# Battery_Operated_Node.net
KiCad netlist of a schematic drawn in Altium Designer
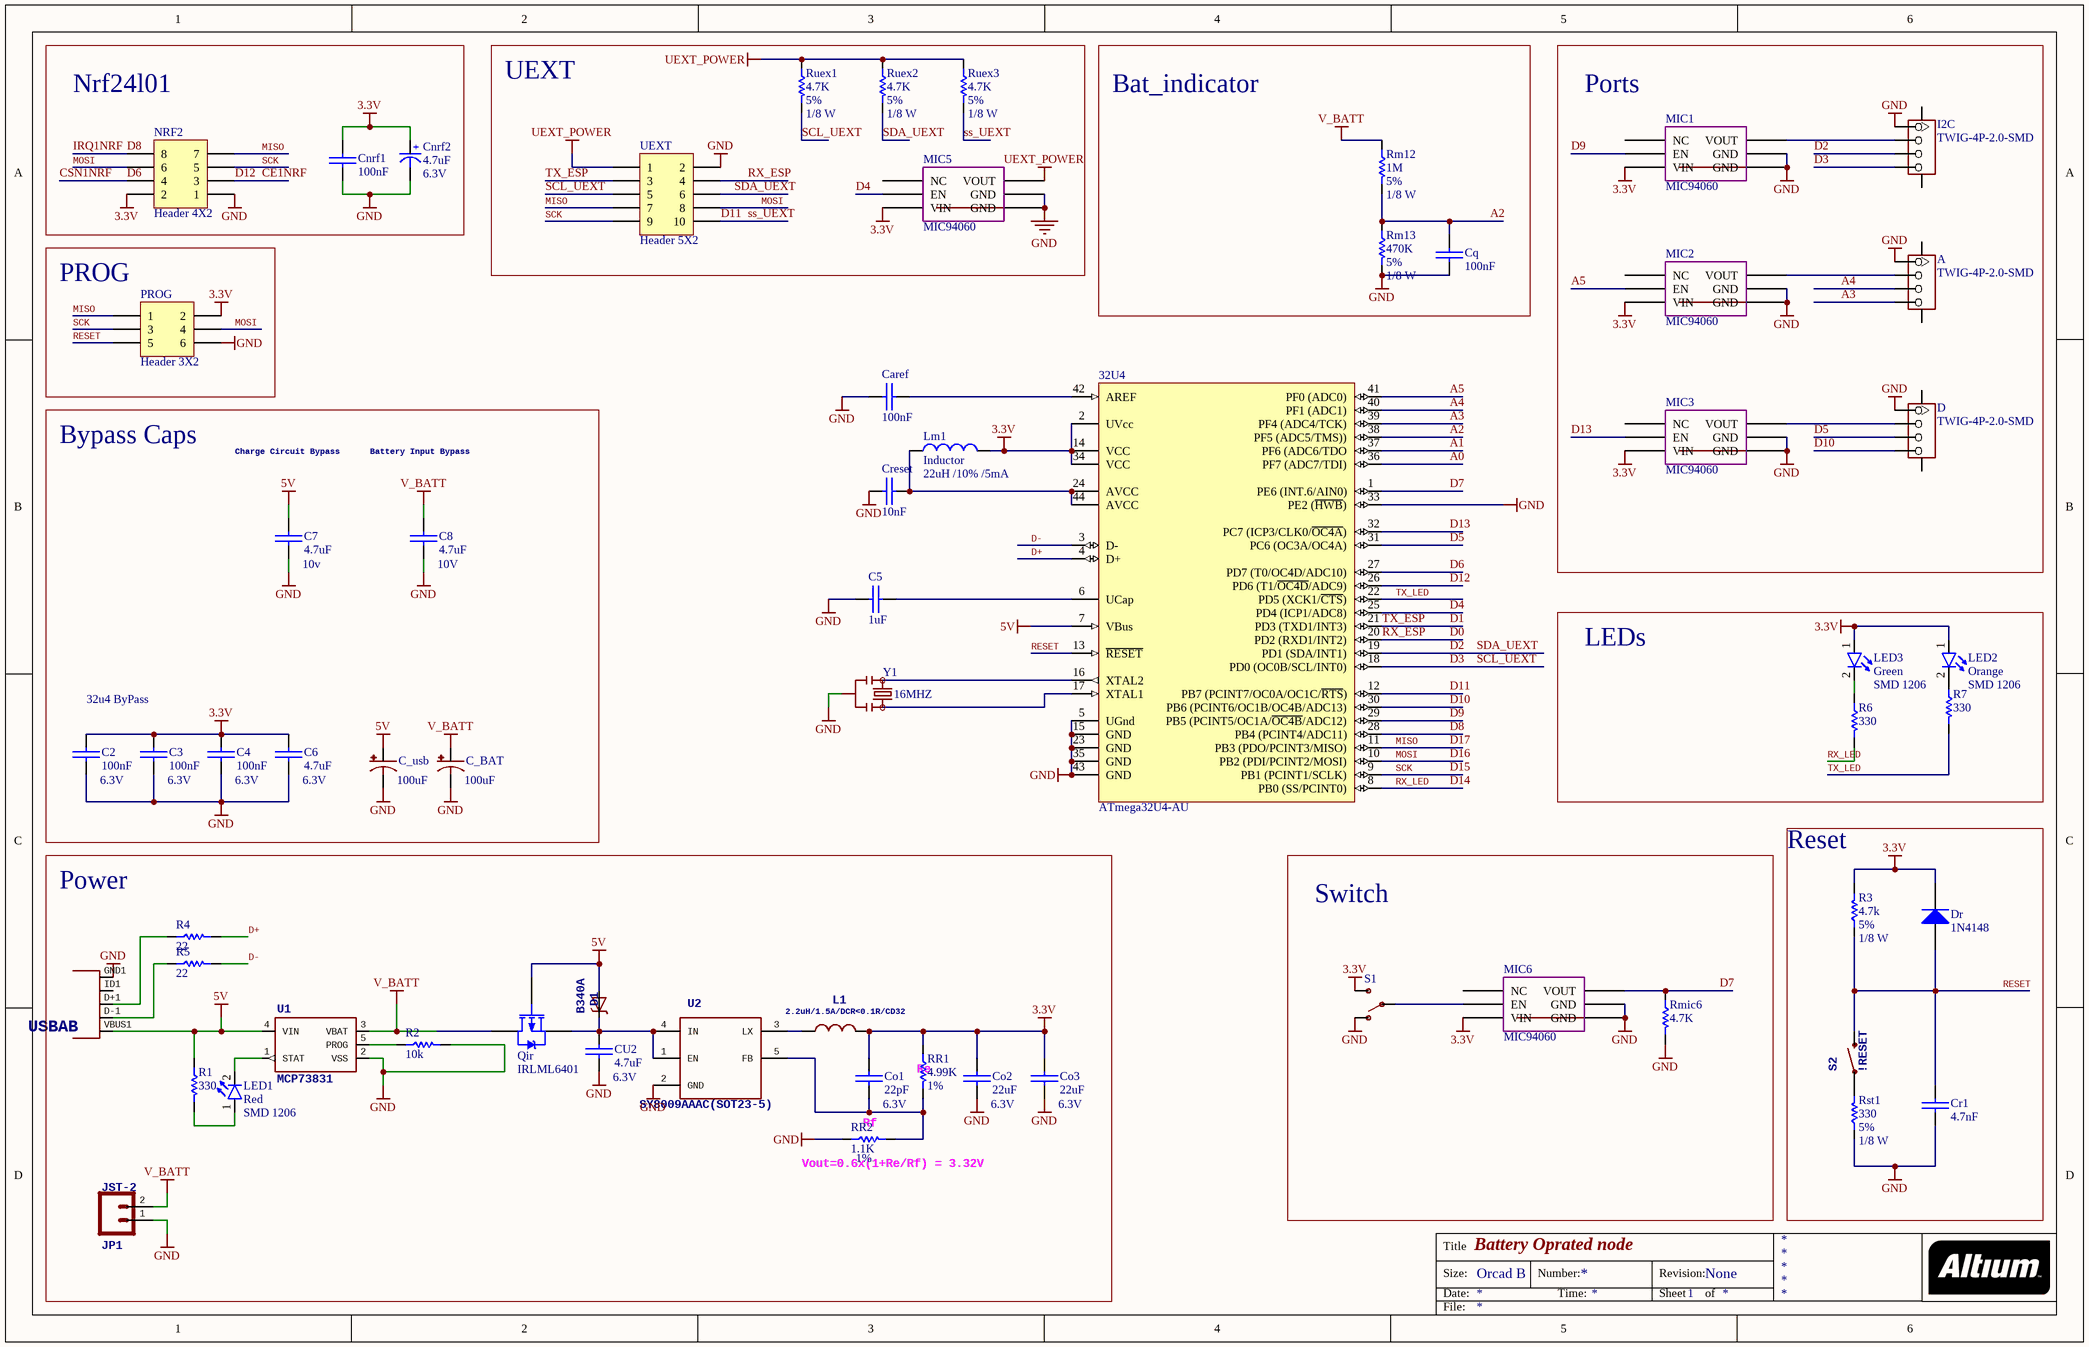
[diagram p0: Battery_Operated Node.SchDoc]

(export (version "E")
  (design (tool "Eeschema 10.0.6"))
  (components
    (comp (ref "32U4")
      (value "ATmega32U4-AU")
      (footprint "44ML_N")
      (description "8-bit AVR Microcontroller, 44-pin TQFP, Industrial Grade (-40°C to 85°C)")
      (fields (field (name "PUBLISHER") "Altium Limited"))
      (libsource (lib "Atmel Microcontroller 8-Bit megaAVR") (part "ATmega32U4-AU"))
    )
    (comp (ref "A")
      (value "TWIG-4P-2.0-SMD")
      (footprint "4P-SMD-2.0")
      (description "part num:1125S-SMT-4P URL: http://oom.lt/J204S")
      (libsource (lib "Connector") (part "TWIG-4P-2.0-SMD-FEMALE-REINFORCE'DD'"))
    )
    (comp (ref "C2")
      (value "100nF")
      (footprint "SMD_CAP_0805")
      (description "ceramic capacitor")
      (fields (field (name "VOLTAGE") "6.3V"))
      (libsource (lib "My Library") (part "Cap-Bipolar"))
    )
    (comp (ref "C3")
      (value "100nF")
      (footprint "SMD_CAP_0805")
      (description "ceramic capacitor")
      (fields (field (name "VOLTAGE") "6.3V"))
      (libsource (lib "My Library") (part "Cap-Bipolar"))
    )
    (comp (ref "C4")
      (value "100nF")
      (footprint "SMD_CAP_0805")
      (description "ceramic capacitor")
      (fields (field (name "VOLTAGE") "6.3V"))
      (libsource (lib "My Library") (part "Cap-Bipolar"))
    )
    (comp (ref "C5")
      (value "1uF")
      (footprint "SMD_CAP_0805")
      (description "ceramic capacitor")
      (fields (field (name "VOLTAGE") "6.3V"))
      (libsource (lib "My Library") (part "Cap-Bipolar"))
    )
    (comp (ref "C6")
      (value "4.7uF")
      (footprint "SMD_CAP_0805")
      (description "ceramic capacitor")
      (fields (field (name "VOLTAGE") "6.3V"))
      (libsource (lib "My Library") (part "Cap-Bipolar"))
    )
    (comp (ref "C7")
      (value "4.7uF")
      (footprint "SMD_CAP_0805")
      (description "ceramic capacitor")
      (fields (field (name "VOLTAGE") "10v"))
      (libsource (lib "My Library") (part "Cap-Bipolar"))
    )
    (comp (ref "C8")
      (value "4.7uF")
      (footprint "SMD_CAP_0805")
      (description "ceramic capacitor")
      (fields (field (name "VOLTAGE") "10V"))
      (libsource (lib "My Library") (part "Cap-Bipolar"))
    )
    (comp (ref "Caref")
      (value "100nF")
      (footprint "SMD_CAP_0805")
      (description "ceramic capacitor")
      (fields (field (name "VOLTAGE") "100V") (field (name "DESIGNER") "Saeid Jorablo"))
      (libsource (lib "My Library") (part "Cap-Bipolar"))
    )
    (comp (ref "Cnrf1")
      (value "100nF")
      (footprint "SMD_CAP_0805")
      (description "ceramic capacitor")
      (fields (field (name "VOLTAGE") "100V") (field (name "DESIGNER") "Saeid Jorablo"))
      (libsource (lib "My Library") (part "Cap-Bipolar"))
    )
    (comp (ref "Cnrf2")
      (value "4.7uF")
      (footprint "CAPP 1206 (3216X18L) Size A")
      (description "Tantalum Capacitor Size A")
      (fields (field (name "VOLTAGE") "6.3V") (field (name "Comment") "4.7uF 6.3V Tantalum"))
      (libsource (lib "My Library") (part "Cap-Polar"))
    )
    (comp (ref "Co1")
      (value "22pF")
      (footprint "SMD_CAP_0805")
      (description "ceramic capacitor")
      (fields (field (name "VOLTAGE") "6.3V"))
      (libsource (lib "My Library") (part "Cap-Bipolar"))
    )
    (comp (ref "Co2")
      (value "22uF")
      (footprint "SMD_CAP_0805")
      (description "ceramic capacitor")
      (fields (field (name "VOLTAGE") "6.3V"))
      (libsource (lib "My Library") (part "Cap-Bipolar"))
    )
    (comp (ref "Co3")
      (value "22uF")
      (footprint "SMD_CAP_0805")
      (description "ceramic capacitor")
      (fields (field (name "VOLTAGE") "6.3V"))
      (libsource (lib "My Library") (part "Cap-Bipolar"))
    )
    (comp (ref "Cq")
      (value "100nF")
      (footprint "SMD_CAP_0805")
      (description "ceramic capacitor")
      (fields (field (name "VOLTAGE") "6.3V"))
      (libsource (lib "My Library") (part "Cap-Bipolar"))
    )
    (comp (ref "Cr1")
      (value "4.7nF")
      (footprint "SMD_CAP_0805")
      (description "ceramic capacitor")
      (fields (field (name "VOLTAGE") "100V") (field (name "DESIGNER") "Saeid Jorablo"))
      (libsource (lib "My Library") (part "Cap-Bipolar"))
    )
    (comp (ref "Creset")
      (value "10nF")
      (footprint "SMD_CAP_0805")
      (description "ceramic capacitor")
      (fields (field (name "VOLTAGE") "100V") (field (name "DESIGNER") "Saeid Jorablo"))
      (libsource (lib "My Library") (part "Cap-Bipolar"))
    )
    (comp (ref "CU2")
      (value "4.7uF")
      (footprint "SMD_CAP_0805")
      (description "ceramic capacitor")
      (fields (field (name "VOLTAGE") "6.3V"))
      (libsource (lib "My Library") (part "Cap-Bipolar"))
    )
    (comp (ref "C_BAT")
      (value "100uF")
      (footprint "PANASONIC_D")
      (description "Polar Capacitor 10V")
      (libsource (lib "SparkFun-Capacitors") (part "CAP_POLD"))
    )
    (comp (ref "C_usb")
      (value "100uF")
      (footprint "PANASONIC_D")
      (description "Polar Capacitor 10V")
      (libsource (lib "SparkFun-Capacitors") (part "CAP_POLD"))
    )
    (comp (ref "D")
      (value "TWIG-4P-2.0-SMD")
      (footprint "4P-SMD-2.0")
      (description "part num:1125S-SMT-4P URL: http://oom.lt/J204S")
      (libsource (lib "Connector") (part "TWIG-4P-2.0-SMD-FEMALE-REINFORCE'DD'"))
    )
    (comp (ref "D1")
      (value "B340A")
      (footprint "SMA-DIODE")
      (libsource (lib "SparkFun-DiscreteSemi") (part "DIODE-SCHOTTKY-B340A"))
    )
    (comp (ref "Dr")
      (value "1N4148")
      (footprint "LL4148")
      (description "High Conductance Fast Diode")
      (fields (field (name "PUBLISHER") "Altium Limited"))
      (libsource (lib "My Library") (part "Diode 1N4148"))
    )
    (comp (ref "I2C")
      (value "TWIG-4P-2.0-SMD")
      (footprint "4P-SMD-2.0")
      (description "part num:1125S-SMT-4P URL: http://oom.lt/J204S")
      (libsource (lib "Connector") (part "TWIG-4P-2.0-SMD-FEMALE-REINFORCE'DD'"))
    )
    (comp (ref "JP1")
      (value "JST-2")
      (footprint "JST-2-SMD")
      (libsource (lib "SparkFun-Connectors") (part "M02-JST-2MM-SMT"))
    )
    (comp (ref "L1")
      (value "2.2uH/1.5A/DCR<0.1R/CD32")
      (footprint "CD32")
      (libsource (lib "OLIMEX_DISCRET") (part "L-CD32"))
    )
    (comp (ref "LED1")
      (value "Red")
      (footprint "LED SMD 1206")
      (description "LED")
      (fields
        (field (name "COLOR") "Red")
        (field (name "SIZE") "SMD 1206")
        (field (name "DESIGNER") "Saeid Jorablo")
      )
      (libsource (lib "My Library") (part "LED"))
    )
    (comp (ref "LED2")
      (value "Orange")
      (footprint "LED SMD 1206")
      (description "LED")
      (fields
        (field (name "COLOR") "Orange")
        (field (name "SIZE") "SMD 1206")
        (field (name "DESIGNER") "Saeid Jorablo")
      )
      (libsource (lib "My Library") (part "LED"))
    )
    (comp (ref "LED3")
      (value "Green")
      (footprint "LED SMD 1206")
      (description "LED")
      (fields
        (field (name "COLOR") "Green")
        (field (name "SIZE") "SMD 1206")
        (field (name "DESIGNER") "Saeid Jorablo")
      )
      (libsource (lib "My Library") (part "LED"))
    )
    (comp (ref "Lm1")
      (value "Inductor")
      (footprint "INDC3216")
      (fields (field (name "ALTIUM_VALUE") "22uH /10% /5mA") (field (name "PUBLISHER") "Altium Limited"))
      (libsource (lib "My Library") (part "Inductor"))
    )
    (comp (ref "MIC1")
      (value "MIC94060")
      (footprint "mic94060")
      (description "MIC94060YC6, SC-70-6")
      (libsource (lib "mic94060") (part "MIC94060"))
    )
    (comp (ref "MIC2")
      (value "MIC94060")
      (footprint "mic94060")
      (description "MIC94060YC6, SC-70-6")
      (libsource (lib "mic94060") (part "MIC94060"))
    )
    (comp (ref "MIC3")
      (value "MIC94060")
      (footprint "mic94060")
      (description "MIC94060YC6, SC-70-6")
      (libsource (lib "mic94060") (part "MIC94060"))
    )
    (comp (ref "MIC5")
      (value "MIC94060")
      (footprint "mic94060")
      (description "MIC94060YC6, SC-70-6")
      (libsource (lib "mic94060") (part "MIC94060"))
    )
    (comp (ref "MIC6")
      (value "MIC94060")
      (footprint "mic94060")
      (description "MIC94060YC6, SC-70-6")
      (libsource (lib "mic94060") (part "MIC94060"))
    )
    (comp (ref "NRF2")
      (value "Header 4X2")
      (footprint "HDR2X4")
      (description "Header, 4-Pin, Dual row")
      (fields (field (name "PUBLISHER") "Altium Limited"))
      (libsource (lib "Miscellaneous Connectors") (part "Header 4X2"))
    )
    (comp (ref "PROG")
      (value "Header 3X2")
      (footprint "HDR2X3")
      (description "Header, 3-Pin, Dual row")
      (fields (field (name "PUBLISHER") "Altium Limited"))
      (libsource (lib "Miscellaneous Connectors") (part "Header 3X2"))
    )
    (comp (ref "Qir")
      (value "IRLML6401")
      (footprint "Micro3_N")
      (description "HEXFET Power MOSFET")
      (fields (field (name "PUBLISHER") "Altium Limited"))
      (libsource (lib "IR Discrete MOSFET - Power") (part "IRLML6401"))
    )
    (comp (ref "R1")
      (value "330")
      (footprint "RES 0805 (2012X06L)")
      (description "Resistor")
      (fields (field (name "TOLERANCE") "5%") (field (name "POWER") "1/8 W"))
      (libsource (lib "My Library") (part "Resistor"))
    )
    (comp (ref "R2")
      (value "10k")
      (footprint "RES 0805 (2012X06L)")
      (description "Resistor")
      (fields (field (name "TOLERANCE") "5%") (field (name "POWER") "1/8 W"))
      (libsource (lib "My Library") (part "Resistor"))
    )
    (comp (ref "R3")
      (value "4.7k")
      (footprint "RES 0805 (2012X06L)")
      (description "Resistor")
      (fields (field (name "TOLERANCE") "5%") (field (name "POWER") "1/8 W"))
      (libsource (lib "My Library") (part "Resistor"))
    )
    (comp (ref "R4")
      (value "22")
      (footprint "RES 0805 (2012X06L)")
      (description "Resistor")
      (fields (field (name "TOLERANCE") "5%") (field (name "POWER") "1/8 W"))
      (libsource (lib "My Library") (part "Resistor"))
    )
    (comp (ref "R5")
      (value "22")
      (footprint "RES 0805 (2012X06L)")
      (description "Resistor")
      (fields (field (name "TOLERANCE") "5%") (field (name "POWER") "1/8 W"))
      (libsource (lib "My Library") (part "Resistor"))
    )
    (comp (ref "R6")
      (value "330")
      (footprint "RES 0805 (2012X06L)")
      (description "Resistor")
      (fields (field (name "TOLERANCE") "5%") (field (name "POWER") "1/8 W"))
      (libsource (lib "My Library") (part "Resistor"))
    )
    (comp (ref "R7")
      (value "330")
      (footprint "RES 0805 (2012X06L)")
      (description "Resistor")
      (fields (field (name "TOLERANCE") "5%") (field (name "POWER") "1/8 W"))
      (libsource (lib "My Library") (part "Resistor"))
    )
    (comp (ref "Rm12")
      (value "1M")
      (footprint "RES 0805 (2012X06L)")
      (description "Resistor")
      (fields (field (name "TOLERANCE") "5%") (field (name "POWER") "1/8 W"))
      (libsource (lib "My Library") (part "Resistor"))
    )
    (comp (ref "Rm13")
      (value "470K")
      (footprint "RES 0805 (2012X06L)")
      (description "Resistor")
      (fields (field (name "TOLERANCE") "5%") (field (name "POWER") "1/8 W"))
      (libsource (lib "My Library") (part "Resistor"))
    )
    (comp (ref "Rmic6")
      (value "4.7K")
      (footprint "RES 0805 (2012X06L)")
      (description "Resistor")
      (fields (field (name "TOLERANCE") "5%") (field (name "POWER") "1/8 W"))
      (libsource (lib "My Library") (part "Resistor"))
    )
    (comp (ref "RR1")
      (value "4.99K")
      (footprint "RES 0805 (2012X06L)")
      (description "Resistor")
      (fields (field (name "TOLERANCE") "1%") (field (name "POWER") "1/8 W"))
      (libsource (lib "My Library") (part "Resistor"))
    )
    (comp (ref "RR2")
      (value "1.1K")
      (footprint "RES 0805 (2012X06L)")
      (description "Resistor")
      (fields (field (name "TOLERANCE") "1%") (field (name "POWER") "1/8 W"))
      (libsource (lib "My Library") (part "Resistor"))
    )
    (comp (ref "Rst1")
      (value "330")
      (footprint "RES 0805 (2012X06L)")
      (description "Resistor")
      (fields (field (name "TOLERANCE") "5%") (field (name "POWER") "1/8 W"))
      (libsource (lib "My Library") (part "Resistor"))
    )
    (comp (ref "Ruex1")
      (value "4.7K")
      (footprint "RES 0805 (2012X06L)")
      (description "Resistor")
      (fields (field (name "TOLERANCE") "5%") (field (name "POWER") "1/8 W"))
      (libsource (lib "My Library") (part "Resistor"))
    )
    (comp (ref "Ruex2")
      (value "4.7K")
      (footprint "RES 0805 (2012X06L)")
      (description "Resistor")
      (fields (field (name "TOLERANCE") "5%") (field (name "POWER") "1/8 W"))
      (libsource (lib "My Library") (part "Resistor"))
    )
    (comp (ref "Ruex3")
      (value "4.7K")
      (footprint "RES 0805 (2012X06L)")
      (description "Resistor")
      (fields (field (name "TOLERANCE") "5%") (field (name "POWER") "1/8 W"))
      (libsource (lib "My Library") (part "Resistor"))
    )
    (comp (ref "S1")
      (value "~")
      (footprint "SWITCH-SPDT-SMD")
      (description "part num:AYZ0102AGRLC or JS102011SAQN")
      (libsource (lib "SparkFun-Electromechanical") (part "SWITCH-SPDTSMD2"))
    )
    (comp (ref "S2")
      (value "!RESET")
      (footprint "TACTILE_SWITCH_SMD")
      (description "Various NO switches- part num:TS-1518S")
      (libsource (lib "SparkFun-Electromechanical") (part "SWITCH-MOMENTARY-2SMD"))
    )
    (comp (ref "U1")
      (value "MCP73831")
      (footprint "SOT23-5")
      (libsource (lib "SparkFun-PowerIC") (part "MCP73831"))
    )
    (comp (ref "U2")
      (value "SY8009AAAC(SOT23-5)")
      (footprint "SOT23-5")
      (libsource (lib "OLIMEX_IC") (part "SY8008"))
    )
    (comp (ref "U5")
      (value "USB AB Connector(micro usb)")
      (footprint "USB-AB-MICRO-SMD_V03")
      (description "part num:1125S-SMT-4P")
      (fields (field (name "USBAB") "USBAB"))
      (libsource (lib "SparkFun-Connectors") (part "USB-ABCONN-11794"))
    )
    (comp (ref "UEXT")
      (value "Header 5X2")
      (footprint "HDR2X5")
      (description "Header, 5-Pin, Dual row")
      (fields (field (name "PUBLISHER") "Altium Limited"))
      (libsource (lib "Miscellaneous Connectors") (part "Header 5X2"))
    )
    (comp (ref "Y1")
      (value "16MHZ")
      (footprint "RESONATOR-SMD")
      (description "Resonator ,Small SMD resonator,Used, eg, on the Arduino Pro/ Pro Mini boards.  16MHz- XTAL-08895")
      (libsource (lib "SparkFun-FreqCtrl") (part "RESONATOR8MHZ"))
    )
  )
  (nets
    (net (code "1") (name "/A0") (class "Default")
      (node (ref "32U4") (pin "36") (pinfunction "PF7_(ADC7/TDI)_36") (pintype "bidirectional"))
    )
    (net (code "2") (name "/A1") (class "Default")
      (node (ref "32U4") (pin "37") (pinfunction "PF6_(ADC6/TDO_37") (pintype "bidirectional"))
    )
    (net (code "3") (name "/A2") (class "Default")
      (node (ref "32U4") (pin "38") (pinfunction "PF5_(ADC5/TMS))_38") (pintype "bidirectional"))
      (node (ref "Cq") (pin "1") (pinfunction "+_1") (pintype "passive"))
      (node (ref "Rm12") (pin "2") (pinfunction "2_2") (pintype "passive"))
      (node (ref "Rm13") (pin "1") (pinfunction "1_1") (pintype "passive"))
    )
    (net (code "4") (name "/A3") (class "Default")
      (node (ref "32U4") (pin "39") (pinfunction "PF4_(ADC4/TCK)_39") (pintype "bidirectional"))
      (node (ref "A") (pin "4") (pinfunction "4_4") (pintype "passive"))
    )
    (net (code "5") (name "/A4") (class "Default")
      (node (ref "32U4") (pin "40") (pinfunction "PF1_(ADC1)_40") (pintype "bidirectional"))
      (node (ref "A") (pin "3") (pinfunction "3_3") (pintype "passive"))
    )
    (net (code "6") (name "/A5") (class "Default")
      (node (ref "32U4") (pin "41") (pinfunction "PF0_(ADC0)_41") (pintype "bidirectional"))
      (node (ref "MIC2") (pin "3") (pinfunction "EN_3") (pintype "passive"))
    )
    (net (code "7") (name "/CE1NRF") (class "Default")
      (node (ref "32U4") (pin "26") (pinfunction "PD6_(T1/~{OC4D}/ADC9)_26") (pintype "bidirectional"))
      (node (ref "NRF2") (pin "3") (pinfunction "3_3") (pintype "passive"))
    )
    (net (code "8") (name "/CSN1NRF") (class "Default")
      (node (ref "32U4") (pin "27") (pinfunction "PD7_(T0/OC4D/ADC10)_27") (pintype "bidirectional"))
      (node (ref "NRF2") (pin "4") (pinfunction "4_4") (pintype "passive"))
    )
    (net (code "9") (name "/D+") (class "Default")
      (node (ref "32U4") (pin "4") (pinfunction "D+_4") (pintype "bidirectional"))
      (node (ref "R4") (pin "2") (pinfunction "2_2") (pintype "passive"))
    )
    (net (code "10") (name "/D-") (class "Default")
      (node (ref "32U4") (pin "3") (pinfunction "D-_3") (pintype "bidirectional"))
      (node (ref "R5") (pin "2") (pinfunction "2_2") (pintype "passive"))
    )
    (net (code "11") (name "/D0") (class "Default")
      (node (ref "32U4") (pin "20") (pinfunction "PD2_(RXD1/INT2)_20") (pintype "bidirectional"))
      (node (ref "UEXT") (pin "4") (pinfunction "4_4") (pintype "passive"))
    )
    (net (code "12") (name "/D1") (class "Default")
      (node (ref "32U4") (pin "21") (pinfunction "PD3_(TXD1/INT3)_21") (pintype "bidirectional"))
      (node (ref "UEXT") (pin "3") (pinfunction "3_3") (pintype "passive"))
    )
    (net (code "13") (name "/D2") (class "Default")
      (node (ref "32U4") (pin "19") (pinfunction "PD1_(SDA/INT1)_19") (pintype "bidirectional"))
      (node (ref "I2C") (pin "3") (pinfunction "3_3") (pintype "passive"))
      (node (ref "Ruex2") (pin "2") (pinfunction "2_2") (pintype "passive"))
      (node (ref "UEXT") (pin "6") (pinfunction "6_6") (pintype "passive"))
    )
    (net (code "14") (name "/D3") (class "Default")
      (node (ref "32U4") (pin "18") (pinfunction "PD0_(OC0B/SCL/INT0)_18") (pintype "bidirectional"))
      (node (ref "I2C") (pin "4") (pinfunction "4_4") (pintype "passive"))
      (node (ref "Ruex1") (pin "2") (pinfunction "2_2") (pintype "passive"))
      (node (ref "UEXT") (pin "5") (pinfunction "5_5") (pintype "passive"))
    )
    (net (code "15") (name "/D4") (class "Default")
      (node (ref "32U4") (pin "25") (pinfunction "PD4_(ICP1/ADC8)_25") (pintype "bidirectional"))
      (node (ref "MIC5") (pin "3") (pinfunction "EN_3") (pintype "passive"))
    )
    (net (code "16") (name "/D5") (class "Default")
      (node (ref "32U4") (pin "31") (pinfunction "PC6_(OC3A/OC4A)_31") (pintype "bidirectional"))
      (node (ref "D") (pin "3") (pinfunction "3_3") (pintype "passive"))
    )
    (net (code "17") (name "/D7") (class "Default")
      (node (ref "32U4") (pin "1") (pinfunction "PE6_(INT.6/AIN0)_1") (pintype "bidirectional"))
      (node (ref "MIC6") (pin "1") (pinfunction "VOUT_1") (pintype "passive"))
      (node (ref "Rmic6") (pin "1") (pinfunction "1_1") (pintype "passive"))
    )
    (net (code "18") (name "/D8") (class "Default")
      (node (ref "32U4") (pin "28") (pinfunction "PB4_(PCINT4/ADC11)_28") (pintype "bidirectional"))
      (node (ref "NRF2") (pin "8") (pinfunction "8_8") (pintype "passive"))
    )
    (net (code "19") (name "/D9") (class "Default")
      (node (ref "32U4") (pin "29") (pinfunction "PB5_(PCINT5/OC1A/~{OC4B}/ADC12)_29") (pintype "bidirectional"))
      (node (ref "MIC1") (pin "3") (pinfunction "EN_3") (pintype "passive"))
    )
    (net (code "20") (name "/D10") (class "Default")
      (node (ref "32U4") (pin "30") (pinfunction "PB6_(PCINT6/OC1B/OC4B/ADC13)_30") (pintype "bidirectional"))
      (node (ref "D") (pin "4") (pinfunction "4_4") (pintype "passive"))
    )
    (net (code "21") (name "/D11") (class "Default")
      (node (ref "32U4") (pin "12") (pinfunction "PB7_(PCINT7/OC0A/OC1C/~{RTS})_12") (pintype "bidirectional"))
      (node (ref "Ruex3") (pin "2") (pinfunction "2_2") (pintype "passive"))
      (node (ref "UEXT") (pin "10") (pinfunction "10_10") (pintype "passive"))
    )
    (net (code "22") (name "/D13") (class "Default")
      (node (ref "32U4") (pin "32") (pinfunction "PC7_(ICP3/CLK0/~{OC4A})_32") (pintype "bidirectional"))
      (node (ref "MIC3") (pin "3") (pinfunction "EN_3") (pintype "passive"))
    )
    (net (code "23") (name "/D14") (class "Default")
      (node (ref "32U4") (pin "8") (pinfunction "PB0_(SS/PCINT0)_8") (pintype "bidirectional"))
      (node (ref "R6") (pin "2") (pinfunction "2_2") (pintype "passive"))
    )
    (net (code "24") (name "/D15") (class "Default")
      (node (ref "32U4") (pin "9") (pinfunction "PB1_(PCINT1/SCLK)_9") (pintype "bidirectional"))
      (node (ref "NRF2") (pin "5") (pinfunction "5_5") (pintype "passive"))
      (node (ref "PROG") (pin "3") (pinfunction "3_3") (pintype "passive"))
      (node (ref "UEXT") (pin "9") (pinfunction "9_9") (pintype "passive"))
    )
    (net (code "25") (name "/D16") (class "Default")
      (node (ref "32U4") (pin "10") (pinfunction "PB2_(PDI/PCINT2/MOSI)_10") (pintype "bidirectional"))
      (node (ref "NRF2") (pin "6") (pinfunction "6_6") (pintype "passive"))
      (node (ref "PROG") (pin "4") (pinfunction "4_4") (pintype "passive"))
      (node (ref "UEXT") (pin "8") (pinfunction "8_8") (pintype "passive"))
    )
    (net (code "26") (name "/D17") (class "Default")
      (node (ref "32U4") (pin "11") (pinfunction "PB3_(PDO/PCINT3/MISO)_11") (pintype "bidirectional"))
      (node (ref "NRF2") (pin "7") (pinfunction "7_7") (pintype "passive"))
      (node (ref "PROG") (pin "1") (pinfunction "1_1") (pintype "passive"))
      (node (ref "UEXT") (pin "7") (pinfunction "7_7") (pintype "passive"))
    )
    (net (code "27") (name "/RESET") (class "Default")
      (node (ref "32U4") (pin "13") (pinfunction "~{RESET}_13") (pintype "input"))
      (node (ref "Cr1") (pin "1") (pinfunction "+_1") (pintype "passive"))
      (node (ref "Dr") (pin "1") (pinfunction "A_1") (pintype "passive"))
      (node (ref "PROG") (pin "5") (pinfunction "5_5") (pintype "passive"))
      (node (ref "R3") (pin "1") (pinfunction "1_1") (pintype "passive"))
      (node (ref "S2") (pin "3") (pinfunction "2_3") (pintype "passive"))
    )
    (net (code "28") (name "/TX_LED") (class "Default")
      (node (ref "32U4") (pin "22") (pinfunction "PD5_(XCK1/~{CTS})_22") (pintype "bidirectional"))
      (node (ref "R7") (pin "2") (pinfunction "2_2") (pintype "passive"))
    )
    (net (code "29") (name "3.3V") (class "Default")
      (node (ref "32U4") (pin "14") (pinfunction "VCC_14") (pintype "power_in"))
      (node (ref "32U4") (pin "2") (pinfunction "UVcc_2") (pintype "power_in"))
      (node (ref "32U4") (pin "34") (pinfunction "VCC_34") (pintype "power_in"))
      (node (ref "C2") (pin "2") (pinfunction "-_2") (pintype "passive"))
      (node (ref "C3") (pin "2") (pinfunction "-_2") (pintype "passive"))
      (node (ref "C4") (pin "2") (pinfunction "-_2") (pintype "passive"))
      (node (ref "C6") (pin "2") (pinfunction "-_2") (pintype "passive"))
      (node (ref "Cnrf1") (pin "1") (pinfunction "+_1") (pintype "passive"))
      (node (ref "Cnrf2") (pin "1") (pinfunction "+_1") (pintype "passive"))
      (node (ref "Co1") (pin "2") (pinfunction "-_2") (pintype "passive"))
      (node (ref "Co2") (pin "2") (pinfunction "-_2") (pintype "passive"))
      (node (ref "Co3") (pin "2") (pinfunction "-_2") (pintype "passive"))
      (node (ref "Dr") (pin "2") (pinfunction "K_2") (pintype "passive"))
      (node (ref "L1") (pin "2") (pinfunction "2_2") (pintype "passive"))
      (node (ref "LED2") (pin "1") (pinfunction "A_1") (pintype "passive"))
      (node (ref "LED3") (pin "1") (pinfunction "A_1") (pintype "passive"))
      (node (ref "Lm1") (pin "2") (pinfunction "2_2") (pintype "passive"))
      (node (ref "MIC1") (pin "4") (pinfunction "VIN_4") (pintype "passive"))
      (node (ref "MIC2") (pin "4") (pinfunction "VIN_4") (pintype "passive"))
      (node (ref "MIC3") (pin "4") (pinfunction "VIN_4") (pintype "passive"))
      (node (ref "MIC5") (pin "4") (pinfunction "VIN_4") (pintype "passive"))
      (node (ref "MIC6") (pin "4") (pinfunction "VIN_4") (pintype "passive"))
      (node (ref "NRF2") (pin "2") (pinfunction "2_2") (pintype "passive"))
      (node (ref "PROG") (pin "2") (pinfunction "2_2") (pintype "passive"))
      (node (ref "R3") (pin "2") (pinfunction "2_2") (pintype "passive"))
      (node (ref "RR1") (pin "1") (pinfunction "1_1") (pintype "passive"))
      (node (ref "S1") (pin "3") (pinfunction "S_3") (pintype "passive"))
    )
    (net (code "30") (name "5V") (class "Default")
      (node (ref "32U4") (pin "7") (pinfunction "VBus_7") (pintype "input"))
      (node (ref "C7") (pin "2") (pinfunction "-_2") (pintype "passive"))
      (node (ref "C_usb") (pin "+") (pinfunction "+_+") (pintype "passive"))
      (node (ref "D1") (pin "A") (pinfunction "A_A") (pintype "passive"))
      (node (ref "Qir") (pin "1") (pinfunction "G_1") (pintype "passive"))
      (node (ref "R1") (pin "1") (pinfunction "1_1") (pintype "passive"))
      (node (ref "U1") (pin "4") (pinfunction "VIN_4") (pintype "power_in"))
      (node (ref "U5") (pin "VBUS1") (pinfunction "VBUS_VBUS1") (pintype "passive"))
    )
    (net (code "31") (name "GND") (class "Default")
      (node (ref "32U4") (pin "15") (pinfunction "GND_15") (pintype "power_in"))
      (node (ref "32U4") (pin "23") (pinfunction "GND_23") (pintype "power_in"))
      (node (ref "32U4") (pin "33") (pinfunction "PE2_(~{HWB})_33") (pintype "bidirectional"))
      (node (ref "32U4") (pin "35") (pinfunction "GND_35") (pintype "power_in"))
      (node (ref "32U4") (pin "43") (pinfunction "GND_43") (pintype "power_in"))
      (node (ref "32U4") (pin "5") (pinfunction "UGnd_5") (pintype "power_in"))
      (node (ref "A") (pin "1") (pinfunction "1_1") (pintype "passive"))
      (node (ref "C2") (pin "1") (pinfunction "+_1") (pintype "passive"))
      (node (ref "C3") (pin "1") (pinfunction "+_1") (pintype "passive"))
      (node (ref "C4") (pin "1") (pinfunction "+_1") (pintype "passive"))
      (node (ref "C5") (pin "1") (pinfunction "+_1") (pintype "passive"))
      (node (ref "C6") (pin "1") (pinfunction "+_1") (pintype "passive"))
      (node (ref "C7") (pin "1") (pinfunction "+_1") (pintype "passive"))
      (node (ref "C8") (pin "1") (pinfunction "+_1") (pintype "passive"))
      (node (ref "CU2") (pin "1") (pinfunction "+_1") (pintype "passive"))
      (node (ref "C_BAT") (pin "-") (pinfunction "-_-") (pintype "passive"))
      (node (ref "C_usb") (pin "-") (pinfunction "-_-") (pintype "passive"))
      (node (ref "Caref") (pin "1") (pinfunction "+_1") (pintype "passive"))
      (node (ref "Cnrf1") (pin "2") (pinfunction "-_2") (pintype "passive"))
      (node (ref "Cnrf2") (pin "2") (pinfunction "-_2") (pintype "passive"))
      (node (ref "Co2") (pin "1") (pinfunction "+_1") (pintype "passive"))
      (node (ref "Co3") (pin "1") (pinfunction "+_1") (pintype "passive"))
      (node (ref "Cq") (pin "2") (pinfunction "-_2") (pintype "passive"))
      (node (ref "Cr1") (pin "2") (pinfunction "-_2") (pintype "passive"))
      (node (ref "Creset") (pin "1") (pinfunction "+_1") (pintype "passive"))
      (node (ref "D") (pin "1") (pinfunction "1_1") (pintype "passive"))
      (node (ref "I2C") (pin "1") (pinfunction "1_1") (pintype "passive"))
      (node (ref "JP1") (pin "1") (pinfunction "2_1") (pintype "passive"))
      (node (ref "MIC1") (pin "2") (pinfunction "GND_2") (pintype "passive"))
      (node (ref "MIC1") (pin "5") (pinfunction "GND_5") (pintype "passive"))
      (node (ref "MIC2") (pin "2") (pinfunction "GND_2") (pintype "passive"))
      (node (ref "MIC2") (pin "5") (pinfunction "GND_5") (pintype "passive"))
      (node (ref "MIC3") (pin "2") (pinfunction "GND_2") (pintype "passive"))
      (node (ref "MIC3") (pin "5") (pinfunction "GND_5") (pintype "passive"))
      (node (ref "MIC5") (pin "2") (pinfunction "GND_2") (pintype "passive"))
      (node (ref "MIC5") (pin "5") (pinfunction "GND_5") (pintype "passive"))
      (node (ref "MIC6") (pin "2") (pinfunction "GND_2") (pintype "passive"))
      (node (ref "MIC6") (pin "5") (pinfunction "GND_5") (pintype "passive"))
      (node (ref "NRF2") (pin "1") (pinfunction "1_1") (pintype "passive"))
      (node (ref "PROG") (pin "6") (pinfunction "6_6") (pintype "passive"))
      (node (ref "R2") (pin "2") (pinfunction "2_2") (pintype "passive"))
      (node (ref "RR2") (pin "1") (pinfunction "1_1") (pintype "passive"))
      (node (ref "Rm13") (pin "2") (pinfunction "2_2") (pintype "passive"))
      (node (ref "Rmic6") (pin "2") (pinfunction "2_2") (pintype "passive"))
      (node (ref "Rst1") (pin "1") (pinfunction "1_1") (pintype "passive"))
      (node (ref "S1") (pin "1") (pinfunction "O_1") (pintype "passive"))
      (node (ref "U1") (pin "2") (pinfunction "VSS_2") (pintype "power_in"))
      (node (ref "U2") (pin "2") (pinfunction "GND_2") (pintype "passive"))
      (node (ref "U5") (pin "GND1") (pinfunction "GND_GND1") (pintype "passive"))
      (node (ref "UEXT") (pin "2") (pinfunction "2_2") (pintype "passive"))
      (node (ref "Y1") (pin "2") (pinfunction "2_2") (pintype "passive"))
    )
    (net (code "32") (name "Net-(32U4-AREF)") (class "Default")
      (node (ref "32U4") (pin "42") (pinfunction "AREF_42") (pintype "input"))
      (node (ref "Caref") (pin "2") (pinfunction "-_2") (pintype "passive"))
    )
    (net (code "33") (name "Net-(32U4-UCap)") (class "Default")
      (node (ref "32U4") (pin "6") (pinfunction "UCap_6") (pintype "passive"))
      (node (ref "C5") (pin "2") (pinfunction "-_2") (pintype "passive"))
    )
    (net (code "34") (name "Net-(32U4-XTAL1)") (class "Default")
      (node (ref "32U4") (pin "17") (pinfunction "XTAL1_17") (pintype "input"))
      (node (ref "Y1") (pin "3") (pinfunction "3_3") (pintype "passive"))
    )
    (net (code "35") (name "Net-(32U4-XTAL2)") (class "Default")
      (node (ref "32U4") (pin "16") (pinfunction "XTAL2_16") (pintype "output"))
      (node (ref "Y1") (pin "1") (pinfunction "1_1") (pintype "passive"))
    )
    (net (code "36") (name "Net-(CU2--)") (class "Default")
      (node (ref "CU2") (pin "2") (pinfunction "-_2") (pintype "passive"))
      (node (ref "D1") (pin "C") (pinfunction "C_C") (pintype "passive"))
      (node (ref "Qir") (pin "2") (pinfunction "S_2") (pintype "passive"))
      (node (ref "U2") (pin "1") (pinfunction "EN_1") (pintype "passive"))
      (node (ref "U2") (pin "4") (pinfunction "IN_4") (pintype "passive"))
    )
    (net (code "37") (name "Net-(Co1-+)") (class "Default")
      (node (ref "Co1") (pin "1") (pinfunction "+_1") (pintype "passive"))
      (node (ref "RR1") (pin "2") (pinfunction "2_2") (pintype "passive"))
      (node (ref "RR2") (pin "2") (pinfunction "2_2") (pintype "passive"))
      (node (ref "U2") (pin "5") (pinfunction "FB_5") (pintype "passive"))
    )
    (net (code "38") (name "Net-(Creset--)") (class "Default")
      (node (ref "32U4") (pin "24") (pinfunction "AVCC_24") (pintype "power_in"))
      (node (ref "32U4") (pin "44") (pinfunction "AVCC_44") (pintype "power_in"))
      (node (ref "Creset") (pin "2") (pinfunction "-_2") (pintype "passive"))
      (node (ref "Lm1") (pin "1") (pinfunction "1_1") (pintype "passive"))
    )
    (net (code "39") (name "Net-(LED1-A)") (class "Default")
      (node (ref "LED1") (pin "1") (pinfunction "A_1") (pintype "passive"))
      (node (ref "R1") (pin "2") (pinfunction "2_2") (pintype "passive"))
    )
    (net (code "40") (name "Net-(LED1-K)") (class "Default")
      (node (ref "LED1") (pin "2") (pinfunction "K_2") (pintype "passive"))
      (node (ref "U1") (pin "1") (pinfunction "STAT_1") (pintype "output"))
    )
    (net (code "41") (name "Net-(LED2-K)") (class "Default")
      (node (ref "LED2") (pin "2") (pinfunction "K_2") (pintype "passive"))
      (node (ref "R7") (pin "1") (pinfunction "1_1") (pintype "passive"))
    )
    (net (code "42") (name "Net-(LED3-K)") (class "Default")
      (node (ref "LED3") (pin "2") (pinfunction "K_2") (pintype "passive"))
      (node (ref "R6") (pin "1") (pinfunction "1_1") (pintype "passive"))
    )
    (net (code "43") (name "Net-(MIC1-VOUT)") (class "Default")
      (node (ref "I2C") (pin "2") (pinfunction "2_2") (pintype "passive"))
      (node (ref "MIC1") (pin "1") (pinfunction "VOUT_1") (pintype "passive"))
    )
    (net (code "44") (name "Net-(MIC2-VOUT)") (class "Default")
      (node (ref "A") (pin "2") (pinfunction "2_2") (pintype "passive"))
      (node (ref "MIC2") (pin "1") (pinfunction "VOUT_1") (pintype "passive"))
    )
    (net (code "45") (name "Net-(MIC3-VOUT)") (class "Default")
      (node (ref "D") (pin "2") (pinfunction "2_2") (pintype "passive"))
      (node (ref "MIC3") (pin "1") (pinfunction "VOUT_1") (pintype "passive"))
    )
    (net (code "46") (name "Net-(MIC6-EN)") (class "Default")
      (node (ref "MIC6") (pin "3") (pinfunction "EN_3") (pintype "passive"))
      (node (ref "S1") (pin "2") (pinfunction "P_2") (pintype "passive"))
    )
    (net (code "47") (name "Net-(Rst1-Pad2)") (class "Default")
      (node (ref "Rst1") (pin "2") (pinfunction "2_2") (pintype "passive"))
      (node (ref "S2") (pin "1") (pinfunction "1_1") (pintype "passive"))
    )
    (net (code "48") (name "Net-(U1-PROG)") (class "Default")
      (node (ref "R2") (pin "1") (pinfunction "1_1") (pintype "passive"))
      (node (ref "U1") (pin "5") (pinfunction "PROG_5") (pintype "passive"))
    )
    (net (code "49") (name "Net-(U2-LX)") (class "Default")
      (node (ref "L1") (pin "1") (pinfunction "1_1") (pintype "passive"))
      (node (ref "U2") (pin "3") (pinfunction "LX_3") (pintype "passive"))
    )
    (net (code "50") (name "Net-(U5-D+)") (class "Default")
      (node (ref "R4") (pin "1") (pinfunction "1_1") (pintype "passive"))
      (node (ref "U5") (pin "D+1") (pinfunction "D+_D+1") (pintype "passive"))
    )
    (net (code "51") (name "Net-(U5-D-)") (class "Default")
      (node (ref "R5") (pin "1") (pinfunction "1_1") (pintype "passive"))
      (node (ref "U5") (pin "D-1") (pinfunction "D-_D-1") (pintype "passive"))
    )
    (net (code "52") (name "UEXT_POWER") (class "Default")
      (node (ref "MIC5") (pin "1") (pinfunction "VOUT_1") (pintype "passive"))
      (node (ref "Ruex1") (pin "1") (pinfunction "1_1") (pintype "passive"))
      (node (ref "Ruex2") (pin "1") (pinfunction "1_1") (pintype "passive"))
      (node (ref "Ruex3") (pin "1") (pinfunction "1_1") (pintype "passive"))
      (node (ref "UEXT") (pin "1") (pinfunction "1_1") (pintype "passive"))
    )
    (net (code "53") (name "V_BATT") (class "Default")
      (node (ref "C8") (pin "2") (pinfunction "-_2") (pintype "passive"))
      (node (ref "C_BAT") (pin "+") (pinfunction "+_+") (pintype "passive"))
      (node (ref "JP1") (pin "2") (pinfunction "1_2") (pintype "passive"))
      (node (ref "Qir") (pin "3") (pinfunction "D_3") (pintype "passive"))
      (node (ref "Rm12") (pin "1") (pinfunction "1_1") (pintype "passive"))
      (node (ref "U1") (pin "3") (pinfunction "VBAT_3") (pintype "power_in"))
    )
    (net (code "54") (name "unconnected-(A-PadSS1)") (class "Default")
      (node (ref "A") (pin "SS1") (pinfunction "SS1_SS1") (pintype "passive"))
    )
    (net (code "55") (name "unconnected-(A-PadSS2)") (class "Default")
      (node (ref "A") (pin "SS2") (pinfunction "SS2_SS2") (pintype "passive"))
    )
    (net (code "56") (name "unconnected-(D-PadSS1)") (class "Default")
      (node (ref "D") (pin "SS1") (pinfunction "SS1_SS1") (pintype "passive"))
    )
    (net (code "57") (name "unconnected-(D-PadSS2)") (class "Default")
      (node (ref "D") (pin "SS2") (pinfunction "SS2_SS2") (pintype "passive"))
    )
    (net (code "58") (name "unconnected-(I2C-PadSS1)") (class "Default")
      (node (ref "I2C") (pin "SS1") (pinfunction "SS1_SS1") (pintype "passive"))
    )
    (net (code "59") (name "unconnected-(I2C-PadSS2)") (class "Default")
      (node (ref "I2C") (pin "SS2") (pinfunction "SS2_SS2") (pintype "passive"))
    )
    (net (code "60") (name "unconnected-(MIC1-NC-Pad6)") (class "Default")
      (node (ref "MIC1") (pin "6") (pinfunction "NC_6") (pintype "passive"))
    )
    (net (code "61") (name "unconnected-(MIC2-NC-Pad6)") (class "Default")
      (node (ref "MIC2") (pin "6") (pinfunction "NC_6") (pintype "passive"))
    )
    (net (code "62") (name "unconnected-(MIC3-NC-Pad6)") (class "Default")
      (node (ref "MIC3") (pin "6") (pinfunction "NC_6") (pintype "passive"))
    )
    (net (code "63") (name "unconnected-(MIC5-NC-Pad6)") (class "Default")
      (node (ref "MIC5") (pin "6") (pinfunction "NC_6") (pintype "passive"))
    )
    (net (code "64") (name "unconnected-(MIC6-NC-Pad6)") (class "Default")
      (node (ref "MIC6") (pin "6") (pinfunction "NC_6") (pintype "passive"))
    )
    (net (code "65") (name "unconnected-(U5-USBID-PadID1)") (class "Default")
      (node (ref "U5") (pin "ID1") (pinfunction "USBID_ID1") (pintype "passive"))
    )
  )
)
